# Alim12_Mot.net
KiCad netlist of a schematic drawn in Altium Designer
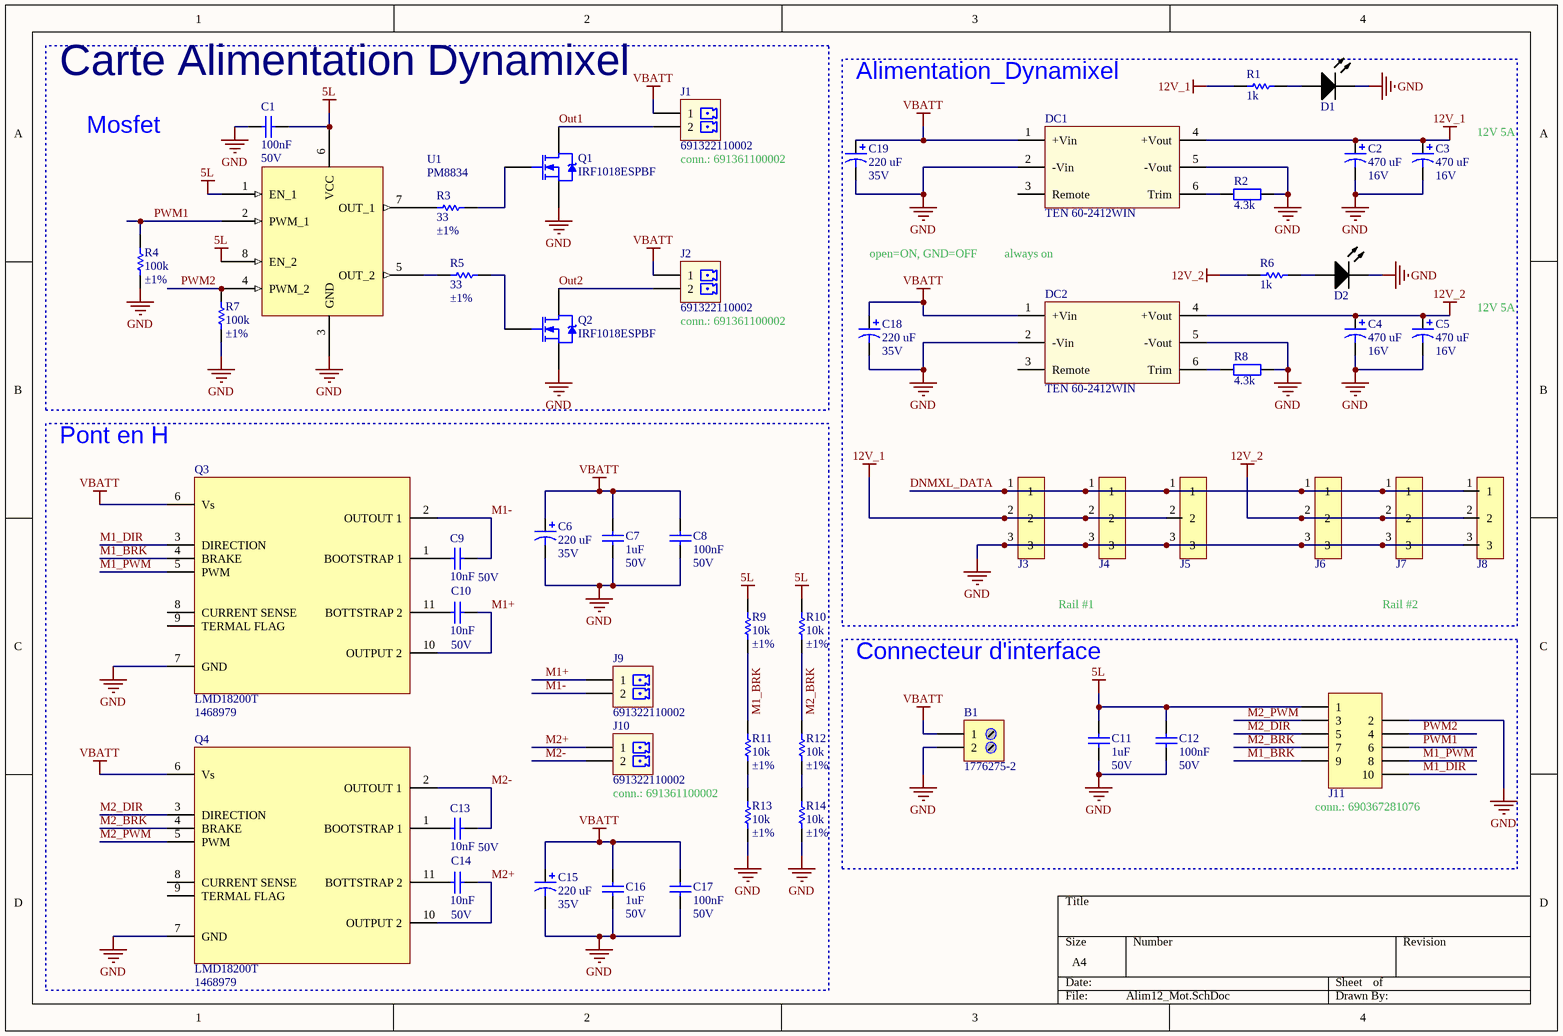
[diagram p0: Alim12_Mot.SchDoc]

(export (version "E")
  (design (tool "Eeschema 10.0.6"))
  (components
    (comp (ref "B1")
      (value "1776275-2")
      (footprint "BORNIER_2V_3.5MM")
      (description "TERM BLOCK 2POS SIDE ENT 3.5MM")
      (fields (field (name "MANUFACTURER") "TE Connectivity AMP Connectors"))
      (libsource (lib "Divers") (part "1776275-2"))
    )
    (comp (ref "C1")
      (value "100nF")
      (footprint "WCAP-CSGP_0603, 1.6x0.8x0.8")
      (description "CAP CER 100nF 50V X7R 0603")
      (fields
        (field (name "MANUFACTURER") "Wurth Elektronik")
        (field (name "MANUFACTURER PART NUMBER") "885012206095")
        (field (name "RATEDVOLTAGE") "50V")
      )
      (libsource (lib "Condensateur") (part "WCAP-CSGP, 885012206095"))
    )
    (comp (ref "C2")
      (value "470 uF")
      (footprint "WCAP-ATG8_8x11.5x3.5x0.5")
      (description "CAP Alu 470 UF 20% 16 V")
      (fields
        (field (name "MANUFACTURER") "Wurth Elektronik")
        (field (name "MANUFACTURER PART NUMBER") "860010374012")
        (field (name "RATEDVOLTAGE") "16V")
      )
      (libsource (lib "Condensateur") (part "WCAP-ATG8, 860010374012"))
    )
    (comp (ref "C3")
      (value "470 uF")
      (footprint "WCAP-ATG8_8x11.5x3.5x0.5")
      (description "CAP Alu 470 UF 20% 16 V")
      (fields
        (field (name "MANUFACTURER") "Wurth Elektronik")
        (field (name "MANUFACTURER PART NUMBER") "860010374012")
        (field (name "RATEDVOLTAGE") "16V")
      )
      (libsource (lib "Condensateur") (part "WCAP-ATG8, 860010374012"))
    )
    (comp (ref "C4")
      (value "470 uF")
      (footprint "WCAP-ATG8_8x11.5x3.5x0.5")
      (description "CAP Alu 470 UF 20% 16 V")
      (fields
        (field (name "MANUFACTURER") "Wurth Elektronik")
        (field (name "MANUFACTURER PART NUMBER") "860010374012")
        (field (name "RATEDVOLTAGE") "16V")
      )
      (libsource (lib "Condensateur") (part "WCAP-ATG8, 860010374012"))
    )
    (comp (ref "C5")
      (value "470 uF")
      (footprint "WCAP-ATG8_8x11.5x3.5x0.5")
      (description "CAP Alu 470 UF 20% 16 V")
      (fields
        (field (name "MANUFACTURER") "Wurth Elektronik")
        (field (name "MANUFACTURER PART NUMBER") "860010374012")
        (field (name "RATEDVOLTAGE") "16V")
      )
      (libsource (lib "Condensateur") (part "WCAP-ATG8, 860010374012"))
    )
    (comp (ref "C6")
      (value "220 uF")
      (footprint "WCAP-ATG8_8x11.5x3.5x0.5")
      (description "CAP Alu 220 UF 20% 35 V")
      (fields
        (field (name "MANUFACTURER") "Wurth Elektronik")
        (field (name "MANUFACTURER PART NUMBER") "860010574011")
        (field (name "RATEDVOLTAGE") "35V")
      )
      (libsource (lib "Condensateur") (part "WCAP-ATG8, 860010574011"))
    )
    (comp (ref "C7")
      (value "1uF")
      (footprint "WCAP-CSGP_0805, 2x1.25x1.25")
      (description "CAP CER 1uF 50V X7R 0805")
      (fields
        (field (name "MANUFACTURER") "Wurth Elektronik")
        (field (name "MANUFACTURER PART NUMBER") "885012207103")
        (field (name "RATEDVOLTAGE") "50V")
      )
      (libsource (lib "Condensateur") (part "WCAP-CSGP, 885012207103"))
    )
    (comp (ref "C8")
      (value "100nF")
      (footprint "WCAP-CSGP_0603, 1.6x0.8x0.8")
      (description "CAP CER 100nF 50V X7R 0603")
      (fields
        (field (name "MANUFACTURER") "Wurth Elektronik")
        (field (name "MANUFACTURER PART NUMBER") "885012206095")
        (field (name "RATEDVOLTAGE") "50V")
      )
      (libsource (lib "Condensateur") (part "WCAP-CSGP, 885012206095"))
    )
    (comp (ref "C9")
      (value "10nF")
      (footprint "WCAP-CSGP_0603, 1.6x0.8x0.8")
      (description "CAP CER 10nF 50V X7R 0603")
      (fields
        (field (name "MANUFACTURER") "Wurth Elektronik")
        (field (name "MANUFACTURER PART NUMBER") "885012206089")
        (field (name "RATEDVOLTAGE") "50V")
      )
      (libsource (lib "Condensateur") (part "WCAP-CSGP, 885012206089"))
    )
    (comp (ref "C10")
      (value "10nF")
      (footprint "WCAP-CSGP_0603, 1.6x0.8x0.8")
      (description "CAP CER 10nF 50V X7R 0603")
      (fields
        (field (name "MANUFACTURER") "Wurth Elektronik")
        (field (name "MANUFACTURER PART NUMBER") "885012206089")
        (field (name "RATEDVOLTAGE") "50V")
      )
      (libsource (lib "Condensateur") (part "WCAP-CSGP, 885012206089"))
    )
    (comp (ref "C11")
      (value "1uF")
      (footprint "WCAP-CSGP_0805, 2x1.25x1.25")
      (description "CAP CER 1uF 50V X7R 0805")
      (fields
        (field (name "MANUFACTURER") "Wurth Elektronik")
        (field (name "MANUFACTURER PART NUMBER") "885012207103")
        (field (name "RATEDVOLTAGE") "50V")
      )
      (libsource (lib "Condensateur") (part "WCAP-CSGP, 885012207103"))
    )
    (comp (ref "C12")
      (value "100nF")
      (footprint "WCAP-CSGP_0603, 1.6x0.8x0.8")
      (description "CAP CER 100nF 50V X7R 0603")
      (fields
        (field (name "MANUFACTURER") "Wurth Elektronik")
        (field (name "MANUFACTURER PART NUMBER") "885012206095")
        (field (name "RATEDVOLTAGE") "50V")
      )
      (libsource (lib "Condensateur") (part "WCAP-CSGP, 885012206095"))
    )
    (comp (ref "C13")
      (value "10nF")
      (footprint "WCAP-CSGP_0603, 1.6x0.8x0.8")
      (description "CAP CER 10nF 50V X7R 0603")
      (fields
        (field (name "MANUFACTURER") "Wurth Elektronik")
        (field (name "MANUFACTURER PART NUMBER") "885012206089")
        (field (name "RATEDVOLTAGE") "50V")
      )
      (libsource (lib "Condensateur") (part "WCAP-CSGP, 885012206089"))
    )
    (comp (ref "C14")
      (value "10nF")
      (footprint "WCAP-CSGP_0603, 1.6x0.8x0.8")
      (description "CAP CER 10nF 50V X7R 0603")
      (fields
        (field (name "MANUFACTURER") "Wurth Elektronik")
        (field (name "MANUFACTURER PART NUMBER") "885012206089")
        (field (name "RATEDVOLTAGE") "50V")
      )
      (libsource (lib "Condensateur") (part "WCAP-CSGP, 885012206089"))
    )
    (comp (ref "C15")
      (value "220 uF")
      (footprint "WCAP-ATG8_8x11.5x3.5x0.5")
      (description "CAP Alu 220 UF 20% 35 V")
      (fields
        (field (name "MANUFACTURER") "Wurth Elektronik")
        (field (name "MANUFACTURER PART NUMBER") "860010574011")
        (field (name "RATEDVOLTAGE") "35V")
      )
      (libsource (lib "Condensateur") (part "WCAP-ATG8, 860010574011"))
    )
    (comp (ref "C16")
      (value "1uF")
      (footprint "WCAP-CSGP_0805, 2x1.25x1.25")
      (description "CAP CER 1uF 50V X7R 0805")
      (fields
        (field (name "MANUFACTURER") "Wurth Elektronik")
        (field (name "MANUFACTURER PART NUMBER") "885012207103")
        (field (name "RATEDVOLTAGE") "50V")
      )
      (libsource (lib "Condensateur") (part "WCAP-CSGP, 885012207103"))
    )
    (comp (ref "C17")
      (value "100nF")
      (footprint "WCAP-CSGP_0603, 1.6x0.8x0.8")
      (description "CAP CER 100nF 50V X7R 0603")
      (fields
        (field (name "MANUFACTURER") "Wurth Elektronik")
        (field (name "MANUFACTURER PART NUMBER") "885012206095")
        (field (name "RATEDVOLTAGE") "50V")
      )
      (libsource (lib "Condensateur") (part "WCAP-CSGP, 885012206095"))
    )
    (comp (ref "C18")
      (value "220 uF")
      (footprint "WCAP-ATG8_8x11.5x3.5x0.5")
      (description "CAP Alu 220 UF 20% 35 V")
      (fields
        (field (name "MANUFACTURER") "Wurth Elektronik")
        (field (name "MANUFACTURER PART NUMBER") "860010574011")
        (field (name "RATEDVOLTAGE") "35V")
      )
      (libsource (lib "Condensateur") (part "WCAP-ATG8, 860010574011"))
    )
    (comp (ref "C19")
      (value "220 uF")
      (footprint "WCAP-ATG8_8x11.5x3.5x0.5")
      (description "CAP Alu 220 UF 20% 35 V")
      (fields
        (field (name "MANUFACTURER") "Wurth Elektronik")
        (field (name "MANUFACTURER PART NUMBER") "860010574011")
        (field (name "RATEDVOLTAGE") "35V")
      )
      (libsource (lib "Condensateur") (part "WCAP-ATG8, 860010574011"))
    )
    (comp (ref "D1")
      (value "LED")
      (footprint "LED_3MM")
      (description "LED 3mm - generique")
      (libsource (lib "Optoélectronique") (part "LED"))
    )
    (comp (ref "D2")
      (value "LED")
      (footprint "LED_3MM")
      (description "LED 3mm - generique")
      (libsource (lib "Optoélectronique") (part "LED"))
    )
    (comp (ref "DC1")
      (value "TEN 60-2412WIN")
      (footprint "TEN 60")
      (description "Traco 12.0V 60W 5A")
      (fields (field (name "MANUFACTURER") "TRACOPOWER"))
      (libsource (lib "Alimentation") (part "TEN 60-2412WIN"))
    )
    (comp (ref "DC2")
      (value "TEN 60-2412WIN")
      (footprint "TEN 60")
      (description "Traco 12.0V 60W 5A")
      (fields (field (name "MANUFACTURER") "TRACOPOWER"))
      (libsource (lib "Alimentation") (part "TEN 60-2412WIN"))
    )
    (comp (ref "J1")
      (value "691322110002")
      (footprint "691322110002")
      (description "TERM BLOCK HDR 2POS 90DEG 3.5MM")
      (fields (field (name "MANUFACTURER") "Wurth Electronics Inc."))
      (libsource (lib "Connecteurs") (part "691322110002"))
    )
    (comp (ref "J2")
      (value "691322110002")
      (footprint "691322110002")
      (description "TERM BLOCK HDR 2POS 90DEG 3.5MM")
      (fields (field (name "MANUFACTURER") "Wurth Electronics Inc."))
      (libsource (lib "Connecteurs") (part "691322110002"))
    )
    (comp (ref "J3")
      (value "22-03-5035")
      (footprint "20-03-5035")
      (libsource (lib "Connecteurs") (part "20-03-5035"))
    )
    (comp (ref "J4")
      (value "22-03-5035")
      (footprint "20-03-5035")
      (libsource (lib "Connecteurs") (part "20-03-5035"))
    )
    (comp (ref "J5")
      (value "22-03-5035")
      (footprint "20-03-5035")
      (libsource (lib "Connecteurs") (part "20-03-5035"))
    )
    (comp (ref "J6")
      (value "22-03-5035")
      (footprint "20-03-5035")
      (libsource (lib "Connecteurs") (part "20-03-5035"))
    )
    (comp (ref "J7")
      (value "22-03-5035")
      (footprint "20-03-5035")
      (libsource (lib "Connecteurs") (part "20-03-5035"))
    )
    (comp (ref "J8")
      (value "22-03-5035")
      (footprint "20-03-5035")
      (libsource (lib "Connecteurs") (part "20-03-5035"))
    )
    (comp (ref "J9")
      (value "691322110002")
      (footprint "691322110002")
      (description "TERM BLOCK HDR 2POS 90DEG 3.5MM")
      (fields (field (name "MANUFACTURER") "Wurth Electronics Inc."))
      (libsource (lib "Connecteurs") (part "691322110002"))
    )
    (comp (ref "J10")
      (value "691322110002")
      (footprint "691322110002")
      (description "TERM BLOCK HDR 2POS 90DEG 3.5MM")
      (fields (field (name "MANUFACTURER") "Wurth Electronics Inc."))
      (libsource (lib "Connecteurs") (part "691322110002"))
    )
    (comp (ref "J11")
      (value "~")
      (footprint "690367281076")
      (description "WR-MM Female SMT Connector with Polarization")
      (fields (field (name "MANUFACTURER PART NUMBER") "690367281076"))
      (libsource (lib "Connecteurs") (part "690367281076"))
    )
    (comp (ref "Q1")
      (value "IRF1018ESPBF")
      (footprint "D2Pak / AAVID 7109DG")
      (description "MOSFET N-CH 60V 79A D2PAK")
      (fields (field (name "MANUFACTURER") "Infineon Technologies"))
      (libsource (lib "Transistors") (part "IRF1018ESPBF"))
    )
    (comp (ref "Q2")
      (value "IRF1018ESPBF")
      (footprint "D2Pak / AAVID 7109DG")
      (description "MOSFET N-CH 60V 79A D2PAK")
      (fields (field (name "MANUFACTURER") "Infineon Technologies"))
      (libsource (lib "Transistors") (part "IRF1018ESPBF"))
    )
    (comp (ref "Q3")
      (value "LMD18200T")
      (footprint "LMD18200T")
      (fields
        (field (name "MANUFACTURER PART NUMBER") "LMD18200T/NOPB")
        (field (name "MANUFACTURER") "TEXAS INSTRUMENTS")
        (field (name "SUPPLIER PART NUMBER 1") "1468979")
      )
      (libsource (lib "Transistors") (part "LMD18200T"))
    )
    (comp (ref "Q4")
      (value "LMD18200T")
      (footprint "LMD18200T")
      (fields
        (field (name "MANUFACTURER PART NUMBER") "LMD18200T/NOPB")
        (field (name "MANUFACTURER") "TEXAS INSTRUMENTS")
        (field (name "SUPPLIER PART NUMBER 1") "1468979")
      )
      (libsource (lib "Transistors") (part "LMD18200T"))
    )
    (comp (ref "R1")
      (value "1k")
      (footprint "RESC1608X06N")
      (description "RES SMD 1K OHM 1% 1/10W 0603")
      (fields
        (field (name "MANUFACTURER") "Yageo")
        (field (name "MANUFACTURER PART NUMBER") "RC0603FR-071KL")
      )
      (libsource (lib "Resistance") (part "RC0603FR-071KL"))
    )
    (comp (ref "R2")
      (value "4.3k")
      (footprint "Resistance:RESC2012X06M")
      (description "RESISTOR")
      (fields
        (field (name "MANUFACTURER") "VISHAY DRALORIC")
        (field (name "MANUFACTURER PART NUMBER") "CRCW08054K30FKEA")
      )
      (libsource (lib "Résistances") (part "any"))
    )
    (comp (ref "R3")
      (value "33")
      (footprint "RESC1608X06N")
      (description "RES SMD 33 OHM 1% 1/10W 0603")
      (fields
        (field (name "MANUFACTURER") "Yageo")
        (field (name "MANUFACTURER PART NUMBER") "RC0603FR-0733RL")
        (field (name "PRECISION") "±1%")
      )
      (libsource (lib "Resistance") (part "RC0603FR-0733RL"))
    )
    (comp (ref "R4")
      (value "100k")
      (footprint "RESC1608X06N")
      (description "RES SMD 100K OHM 1% 1/10W 0603")
      (fields
        (field (name "MANUFACTURER") "Yageo")
        (field (name "MANUFACTURER PART NUMBER") "RC0603FR-07100KL")
        (field (name "PRECISION") "±1%")
      )
      (libsource (lib "Resistance") (part "RC0603FR-07100KL"))
    )
    (comp (ref "R5")
      (value "33")
      (footprint "RESC1608X06N")
      (description "RES SMD 33 OHM 1% 1/10W 0603")
      (fields
        (field (name "MANUFACTURER") "Yageo")
        (field (name "MANUFACTURER PART NUMBER") "RC0603FR-0733RL")
        (field (name "PRECISION") "±1%")
      )
      (libsource (lib "Resistance") (part "RC0603FR-0733RL"))
    )
    (comp (ref "R6")
      (value "1k")
      (footprint "RESC1608X06N")
      (description "RES SMD 1K OHM 1% 1/10W 0603")
      (fields
        (field (name "MANUFACTURER") "Yageo")
        (field (name "MANUFACTURER PART NUMBER") "RC0603FR-071KL")
      )
      (libsource (lib "Resistance") (part "RC0603FR-071KL"))
    )
    (comp (ref "R7")
      (value "100k")
      (footprint "RESC1608X06N")
      (description "RES SMD 100K OHM 1% 1/10W 0603")
      (fields
        (field (name "MANUFACTURER") "Yageo")
        (field (name "MANUFACTURER PART NUMBER") "RC0603FR-07100KL")
        (field (name "PRECISION") "±1%")
      )
      (libsource (lib "Resistance") (part "RC0603FR-07100KL"))
    )
    (comp (ref "R8")
      (value "4.3k")
      (footprint "Resistance:RESC2012X06M")
      (description "RESISTOR")
      (fields
        (field (name "MANUFACTURER") "VISHAY DRALORIC")
        (field (name "MANUFACTURER PART NUMBER") "CRCW08054K30FKEA")
      )
      (libsource (lib "Résistances") (part "any"))
    )
    (comp (ref "R9")
      (value "10k")
      (footprint "RESC1608X06N")
      (description "RES SMD 10K OHM 1% 1/10W 0603")
      (fields
        (field (name "MANUFACTURER") "Yageo")
        (field (name "MANUFACTURER PART NUMBER") "RC0603FR-0710KL")
        (field (name "PRECISION") "±1%")
      )
      (libsource (lib "Resistance") (part "RC0603FR-0710KL"))
    )
    (comp (ref "R10")
      (value "10k")
      (footprint "RESC1608X06N")
      (description "RES SMD 10K OHM 1% 1/10W 0603")
      (fields
        (field (name "MANUFACTURER") "Yageo")
        (field (name "MANUFACTURER PART NUMBER") "RC0603FR-0710KL")
        (field (name "PRECISION") "±1%")
      )
      (libsource (lib "Resistance") (part "RC0603FR-0710KL"))
    )
    (comp (ref "R11")
      (value "10k")
      (footprint "RESC1608X06N")
      (description "RES SMD 10K OHM 1% 1/10W 0603")
      (fields
        (field (name "MANUFACTURER") "Yageo")
        (field (name "MANUFACTURER PART NUMBER") "RC0603FR-0710KL")
        (field (name "PRECISION") "±1%")
      )
      (libsource (lib "Resistance") (part "RC0603FR-0710KL"))
    )
    (comp (ref "R12")
      (value "10k")
      (footprint "RESC1608X06N")
      (description "RES SMD 10K OHM 1% 1/10W 0603")
      (fields
        (field (name "MANUFACTURER") "Yageo")
        (field (name "MANUFACTURER PART NUMBER") "RC0603FR-0710KL")
        (field (name "PRECISION") "±1%")
      )
      (libsource (lib "Resistance") (part "RC0603FR-0710KL"))
    )
    (comp (ref "R13")
      (value "10k")
      (footprint "RESC1608X06N")
      (description "RES SMD 10K OHM 1% 1/10W 0603")
      (fields
        (field (name "MANUFACTURER") "Yageo")
        (field (name "MANUFACTURER PART NUMBER") "RC0603FR-0710KL")
        (field (name "PRECISION") "±1%")
      )
      (libsource (lib "Resistance") (part "RC0603FR-0710KL"))
    )
    (comp (ref "R14")
      (value "10k")
      (footprint "RESC1608X06N")
      (description "RES SMD 10K OHM 1% 1/10W 0603")
      (fields
        (field (name "MANUFACTURER") "Yageo")
        (field (name "MANUFACTURER PART NUMBER") "RC0603FR-0710KL")
        (field (name "PRECISION") "±1%")
      )
      (libsource (lib "Resistance") (part "RC0603FR-0710KL"))
    )
    (comp (ref "U1")
      (value "PM8834")
      (footprint "SOIC127P600X175-8N")
      (description "IC MOSFET DVR 4A DUAL 8SOIC")
      (fields (field (name "MANUFACTURER") "STMicroelectronics"))
      (libsource (lib "CI") (part "PM8834"))
    )
  )
  (nets
    (net (code "1") (name "/DNMXL_DATA") (class "Default")
      (node (ref "J3") (pin "1") (pinfunction "1_1") (pintype "passive"))
      (node (ref "J4") (pin "1") (pinfunction "1_1") (pintype "passive"))
      (node (ref "J5") (pin "1") (pinfunction "1_1") (pintype "passive"))
      (node (ref "J6") (pin "1") (pinfunction "1_1") (pintype "passive"))
      (node (ref "J7") (pin "1") (pinfunction "1_1") (pintype "passive"))
      (node (ref "J8") (pin "1") (pinfunction "1_1") (pintype "passive"))
    )
    (net (code "2") (name "/M1+") (class "Default")
      (node (ref "C10") (pin "2") (pinfunction "2_2") (pintype "passive"))
      (node (ref "J9") (pin "1") (pinfunction "1_1") (pintype "passive"))
      (node (ref "Q3") (pin "10") (pinfunction "OUTPUT_2_10") (pintype "passive"))
    )
    (net (code "3") (name "/M1-") (class "Default")
      (node (ref "C9") (pin "2") (pinfunction "2_2") (pintype "passive"))
      (node (ref "J9") (pin "2") (pinfunction "2_2") (pintype "passive"))
      (node (ref "Q3") (pin "2") (pinfunction "OUTOUT_1_2") (pintype "passive"))
    )
    (net (code "4") (name "/M1_BRK") (class "Default")
      (node (ref "J11") (pin "9") (pinfunction "9_9") (pintype "passive"))
      (node (ref "Q3") (pin "4") (pinfunction "BRAKE_4") (pintype "passive"))
      (node (ref "R11") (pin "2") (pinfunction "2_2") (pintype "passive"))
      (node (ref "R9") (pin "1") (pinfunction "1_1") (pintype "passive"))
    )
    (net (code "5") (name "/M1_DIR") (class "Default")
      (node (ref "J11") (pin "10") (pinfunction "10_10") (pintype "passive"))
      (node (ref "Q3") (pin "3") (pinfunction "DIRECTION_3") (pintype "passive"))
    )
    (net (code "6") (name "/M1_PWM") (class "Default")
      (node (ref "J11") (pin "8") (pinfunction "8_8") (pintype "passive"))
      (node (ref "Q3") (pin "5") (pinfunction "PWM_5") (pintype "passive"))
    )
    (net (code "7") (name "/M2+") (class "Default")
      (node (ref "C14") (pin "2") (pinfunction "2_2") (pintype "passive"))
      (node (ref "J10") (pin "1") (pinfunction "1_1") (pintype "passive"))
      (node (ref "Q4") (pin "10") (pinfunction "OUTPUT_2_10") (pintype "passive"))
    )
    (net (code "8") (name "/M2-") (class "Default")
      (node (ref "C13") (pin "2") (pinfunction "2_2") (pintype "passive"))
      (node (ref "J10") (pin "2") (pinfunction "2_2") (pintype "passive"))
      (node (ref "Q4") (pin "2") (pinfunction "OUTOUT_1_2") (pintype "passive"))
    )
    (net (code "9") (name "/M2_BRK") (class "Default")
      (node (ref "J11") (pin "7") (pinfunction "7_7") (pintype "passive"))
      (node (ref "Q4") (pin "4") (pinfunction "BRAKE_4") (pintype "passive"))
      (node (ref "R10") (pin "1") (pinfunction "1_1") (pintype "passive"))
      (node (ref "R12") (pin "2") (pinfunction "2_2") (pintype "passive"))
    )
    (net (code "10") (name "/M2_DIR") (class "Default")
      (node (ref "J11") (pin "5") (pinfunction "5_5") (pintype "passive"))
      (node (ref "Q4") (pin "3") (pinfunction "DIRECTION_3") (pintype "passive"))
    )
    (net (code "11") (name "/M2_PWM") (class "Default")
      (node (ref "J11") (pin "3") (pinfunction "3_3") (pintype "passive"))
      (node (ref "Q4") (pin "5") (pinfunction "PWM_5") (pintype "passive"))
    )
    (net (code "12") (name "/Out1") (class "Default")
      (node (ref "J1") (pin "2") (pinfunction "2_2") (pintype "passive"))
      (node (ref "Q1") (pin "2") (pinfunction "D_2") (pintype "passive"))
    )
    (net (code "13") (name "/Out2") (class "Default")
      (node (ref "J2") (pin "2") (pinfunction "2_2") (pintype "passive"))
      (node (ref "Q2") (pin "2") (pinfunction "D_2") (pintype "passive"))
    )
    (net (code "14") (name "/PWM1") (class "Default")
      (node (ref "J11") (pin "6") (pinfunction "6_6") (pintype "passive"))
      (node (ref "R4") (pin "2") (pinfunction "2_2") (pintype "passive"))
      (node (ref "U1") (pin "2") (pinfunction "PWM_1_2") (pintype "input"))
    )
    (net (code "15") (name "/PWM2") (class "Default")
      (node (ref "J11") (pin "4") (pinfunction "4_4") (pintype "passive"))
      (node (ref "R7") (pin "2") (pinfunction "2_2") (pintype "passive"))
      (node (ref "U1") (pin "4") (pinfunction "PWM_2_4") (pintype "input"))
    )
    (net (code "16") (name "5L") (class "Default")
      (node (ref "C1") (pin "2") (pinfunction "2_2") (pintype "passive"))
      (node (ref "C11") (pin "2") (pinfunction "2_2") (pintype "passive"))
      (node (ref "C12") (pin "2") (pinfunction "2_2") (pintype "passive"))
      (node (ref "J11") (pin "1") (pinfunction "1_1") (pintype "passive"))
      (node (ref "R10") (pin "2") (pinfunction "2_2") (pintype "passive"))
      (node (ref "R9") (pin "2") (pinfunction "2_2") (pintype "passive"))
      (node (ref "U1") (pin "1") (pinfunction "EN_1_1") (pintype "input"))
      (node (ref "U1") (pin "6") (pinfunction "VCC_6") (pintype "power_in"))
      (node (ref "U1") (pin "8") (pinfunction "EN_2_8") (pintype "input"))
    )
    (net (code "17") (name "12V_1") (class "Default")
      (node (ref "C2") (pin "1") (pinfunction "1_1") (pintype "passive"))
      (node (ref "C3") (pin "1") (pinfunction "1_1") (pintype "passive"))
      (node (ref "DC1") (pin "4") (pinfunction "+Vout_4") (pintype "power_in"))
      (node (ref "J3") (pin "2") (pinfunction "2_2") (pintype "passive"))
      (node (ref "J4") (pin "2") (pinfunction "2_2") (pintype "passive"))
      (node (ref "J5") (pin "2") (pinfunction "2_2") (pintype "passive"))
      (node (ref "R1") (pin "1") (pinfunction "1_1") (pintype "passive"))
    )
    (net (code "18") (name "12V_2") (class "Default")
      (node (ref "C4") (pin "1") (pinfunction "1_1") (pintype "passive"))
      (node (ref "C5") (pin "1") (pinfunction "1_1") (pintype "passive"))
      (node (ref "DC2") (pin "4") (pinfunction "+Vout_4") (pintype "power_in"))
      (node (ref "J6") (pin "2") (pinfunction "2_2") (pintype "passive"))
      (node (ref "J7") (pin "2") (pinfunction "2_2") (pintype "passive"))
      (node (ref "J8") (pin "2") (pinfunction "2_2") (pintype "passive"))
      (node (ref "R6") (pin "1") (pinfunction "1_1") (pintype "passive"))
    )
    (net (code "19") (name "GND") (class "Default")
      (node (ref "B1") (pin "2") (pinfunction "2_2") (pintype "passive"))
      (node (ref "C1") (pin "1") (pinfunction "1_1") (pintype "passive"))
      (node (ref "C11") (pin "1") (pinfunction "1_1") (pintype "passive"))
      (node (ref "C12") (pin "1") (pinfunction "1_1") (pintype "passive"))
      (node (ref "C15") (pin "2") (pinfunction "2_2") (pintype "passive"))
      (node (ref "C16") (pin "1") (pinfunction "1_1") (pintype "passive"))
      (node (ref "C17") (pin "1") (pinfunction "1_1") (pintype "passive"))
      (node (ref "C18") (pin "2") (pinfunction "2_2") (pintype "passive"))
      (node (ref "C19") (pin "2") (pinfunction "2_2") (pintype "passive"))
      (node (ref "C2") (pin "2") (pinfunction "2_2") (pintype "passive"))
      (node (ref "C3") (pin "2") (pinfunction "2_2") (pintype "passive"))
      (node (ref "C4") (pin "2") (pinfunction "2_2") (pintype "passive"))
      (node (ref "C5") (pin "2") (pinfunction "2_2") (pintype "passive"))
      (node (ref "C6") (pin "2") (pinfunction "2_2") (pintype "passive"))
      (node (ref "C7") (pin "1") (pinfunction "1_1") (pintype "passive"))
      (node (ref "C8") (pin "1") (pinfunction "1_1") (pintype "passive"))
      (node (ref "D1") (pin "2") (pinfunction "C_2") (pintype "passive"))
      (node (ref "D2") (pin "2") (pinfunction "C_2") (pintype "passive"))
      (node (ref "DC1") (pin "2") (pinfunction "-Vin_2") (pintype "power_in"))
      (node (ref "DC1") (pin "5") (pinfunction "-Vout_5") (pintype "power_in"))
      (node (ref "DC2") (pin "2") (pinfunction "-Vin_2") (pintype "power_in"))
      (node (ref "DC2") (pin "5") (pinfunction "-Vout_5") (pintype "power_in"))
      (node (ref "J11") (pin "2") (pinfunction "2_2") (pintype "passive"))
      (node (ref "J3") (pin "3") (pinfunction "3_3") (pintype "passive"))
      (node (ref "J4") (pin "3") (pinfunction "3_3") (pintype "passive"))
      (node (ref "J5") (pin "3") (pinfunction "3_3") (pintype "passive"))
      (node (ref "J6") (pin "3") (pinfunction "3_3") (pintype "passive"))
      (node (ref "J7") (pin "3") (pinfunction "3_3") (pintype "passive"))
      (node (ref "J8") (pin "3") (pinfunction "3_3") (pintype "passive"))
      (node (ref "Q1") (pin "3") (pinfunction "S_3") (pintype "passive"))
      (node (ref "Q2") (pin "3") (pinfunction "S_3") (pintype "passive"))
      (node (ref "Q3") (pin "7") (pinfunction "GND_7") (pintype "passive"))
      (node (ref "Q4") (pin "7") (pinfunction "GND_7") (pintype "passive"))
      (node (ref "R13") (pin "1") (pinfunction "1_1") (pintype "passive"))
      (node (ref "R14") (pin "1") (pinfunction "1_1") (pintype "passive"))
      (node (ref "R2") (pin "1") (pinfunction "1_1") (pintype "passive"))
      (node (ref "R4") (pin "1") (pinfunction "1_1") (pintype "passive"))
      (node (ref "R7") (pin "1") (pinfunction "1_1") (pintype "passive"))
      (node (ref "R8") (pin "1") (pinfunction "1_1") (pintype "passive"))
      (node (ref "U1") (pin "3") (pinfunction "GND_3") (pintype "power_in"))
    )
    (net (code "20") (name "Net-(D1-A)") (class "Default")
      (node (ref "D1") (pin "1") (pinfunction "A_1") (pintype "passive"))
      (node (ref "R1") (pin "2") (pinfunction "2_2") (pintype "passive"))
    )
    (net (code "21") (name "Net-(D2-A)") (class "Default")
      (node (ref "D2") (pin "1") (pinfunction "A_1") (pintype "passive"))
      (node (ref "R6") (pin "2") (pinfunction "2_2") (pintype "passive"))
    )
    (net (code "22") (name "Net-(DC1-Trim)") (class "Default")
      (node (ref "DC1") (pin "6") (pinfunction "Trim_6") (pintype "power_in"))
      (node (ref "R2") (pin "2") (pinfunction "2_2") (pintype "passive"))
    )
    (net (code "23") (name "Net-(DC2-Trim)") (class "Default")
      (node (ref "DC2") (pin "6") (pinfunction "Trim_6") (pintype "power_in"))
      (node (ref "R8") (pin "2") (pinfunction "2_2") (pintype "passive"))
    )
    (net (code "24") (name "Net-(Q1-G)") (class "Default")
      (node (ref "Q1") (pin "1") (pinfunction "G_1") (pintype "passive"))
      (node (ref "R3") (pin "2") (pinfunction "2_2") (pintype "passive"))
    )
    (net (code "25") (name "Net-(Q2-G)") (class "Default")
      (node (ref "Q2") (pin "1") (pinfunction "G_1") (pintype "passive"))
      (node (ref "R5") (pin "2") (pinfunction "2_2") (pintype "passive"))
    )
    (net (code "26") (name "Net-(Q3-BOOTSTRAP_1)") (class "Default")
      (node (ref "C9") (pin "1") (pinfunction "1_1") (pintype "passive"))
      (node (ref "Q3") (pin "1") (pinfunction "BOOTSTRAP_1_1") (pintype "passive"))
    )
    (net (code "27") (name "Net-(Q3-BOTTSTRAP_2)") (class "Default")
      (node (ref "C10") (pin "1") (pinfunction "1_1") (pintype "passive"))
      (node (ref "Q3") (pin "11") (pinfunction "BOTTSTRAP_2_11") (pintype "passive"))
    )
    (net (code "28") (name "Net-(Q4-BOOTSTRAP_1)") (class "Default")
      (node (ref "C13") (pin "1") (pinfunction "1_1") (pintype "passive"))
      (node (ref "Q4") (pin "1") (pinfunction "BOOTSTRAP_1_1") (pintype "passive"))
    )
    (net (code "29") (name "Net-(Q4-BOTTSTRAP_2)") (class "Default")
      (node (ref "C14") (pin "1") (pinfunction "1_1") (pintype "passive"))
      (node (ref "Q4") (pin "11") (pinfunction "BOTTSTRAP_2_11") (pintype "passive"))
    )
    (net (code "30") (name "Net-(R11-Pad1)") (class "Default")
      (node (ref "R11") (pin "1") (pinfunction "1_1") (pintype "passive"))
      (node (ref "R13") (pin "2") (pinfunction "2_2") (pintype "passive"))
    )
    (net (code "31") (name "Net-(R12-Pad1)") (class "Default")
      (node (ref "R12") (pin "1") (pinfunction "1_1") (pintype "passive"))
      (node (ref "R14") (pin "2") (pinfunction "2_2") (pintype "passive"))
    )
    (net (code "32") (name "Net-(U1-OUT_1)") (class "Default")
      (node (ref "R3") (pin "1") (pinfunction "1_1") (pintype "passive"))
      (node (ref "U1") (pin "7") (pinfunction "OUT_1_7") (pintype "output"))
    )
    (net (code "33") (name "Net-(U1-OUT_2)") (class "Default")
      (node (ref "R5") (pin "1") (pinfunction "1_1") (pintype "passive"))
      (node (ref "U1") (pin "5") (pinfunction "OUT_2_5") (pintype "output"))
    )
    (net (code "34") (name "VBATT") (class "Default")
      (node (ref "B1") (pin "1") (pinfunction "1_1") (pintype "passive"))
      (node (ref "C15") (pin "1") (pinfunction "1_1") (pintype "passive"))
      (node (ref "C16") (pin "2") (pinfunction "2_2") (pintype "passive"))
      (node (ref "C17") (pin "2") (pinfunction "2_2") (pintype "passive"))
      (node (ref "C18") (pin "1") (pinfunction "1_1") (pintype "passive"))
      (node (ref "C19") (pin "1") (pinfunction "1_1") (pintype "passive"))
      (node (ref "C6") (pin "1") (pinfunction "1_1") (pintype "passive"))
      (node (ref "C7") (pin "2") (pinfunction "2_2") (pintype "passive"))
      (node (ref "C8") (pin "2") (pinfunction "2_2") (pintype "passive"))
      (node (ref "DC1") (pin "1") (pinfunction "+Vin_1") (pintype "power_in"))
      (node (ref "DC2") (pin "1") (pinfunction "+Vin_1") (pintype "power_in"))
      (node (ref "J1") (pin "1") (pinfunction "1_1") (pintype "passive"))
      (node (ref "J2") (pin "1") (pinfunction "1_1") (pintype "passive"))
      (node (ref "Q3") (pin "6") (pinfunction "Vs_6") (pintype "passive"))
      (node (ref "Q4") (pin "6") (pinfunction "Vs_6") (pintype "passive"))
    )
    (net (code "35") (name "unconnected-(DC1-Remote-Pad3)") (class "Default")
      (node (ref "DC1") (pin "3") (pinfunction "Remote_3") (pintype "power_in"))
    )
    (net (code "36") (name "unconnected-(DC2-Remote-Pad3)") (class "Default")
      (node (ref "DC2") (pin "3") (pinfunction "Remote_3") (pintype "power_in"))
    )
    (net (code "37") (name "unconnected-(Q3-CURRENT_SENSE-Pad8)") (class "Default")
      (node (ref "Q3") (pin "8") (pinfunction "CURRENT_SENSE_8") (pintype "passive"))
    )
    (net (code "38") (name "unconnected-(Q3-TERMAL_FLAG-Pad9)") (class "Default")
      (node (ref "Q3") (pin "9") (pinfunction "TERMAL_FLAG_9") (pintype "passive"))
    )
    (net (code "39") (name "unconnected-(Q4-CURRENT_SENSE-Pad8)") (class "Default")
      (node (ref "Q4") (pin "8") (pinfunction "CURRENT_SENSE_8") (pintype "passive"))
    )
    (net (code "40") (name "unconnected-(Q4-TERMAL_FLAG-Pad9)") (class "Default")
      (node (ref "Q4") (pin "9") (pinfunction "TERMAL_FLAG_9") (pintype "passive"))
    )
  )
)
